# make_etf_great_again.net
KiCad netlist of a schematic drawn in Altium Designer
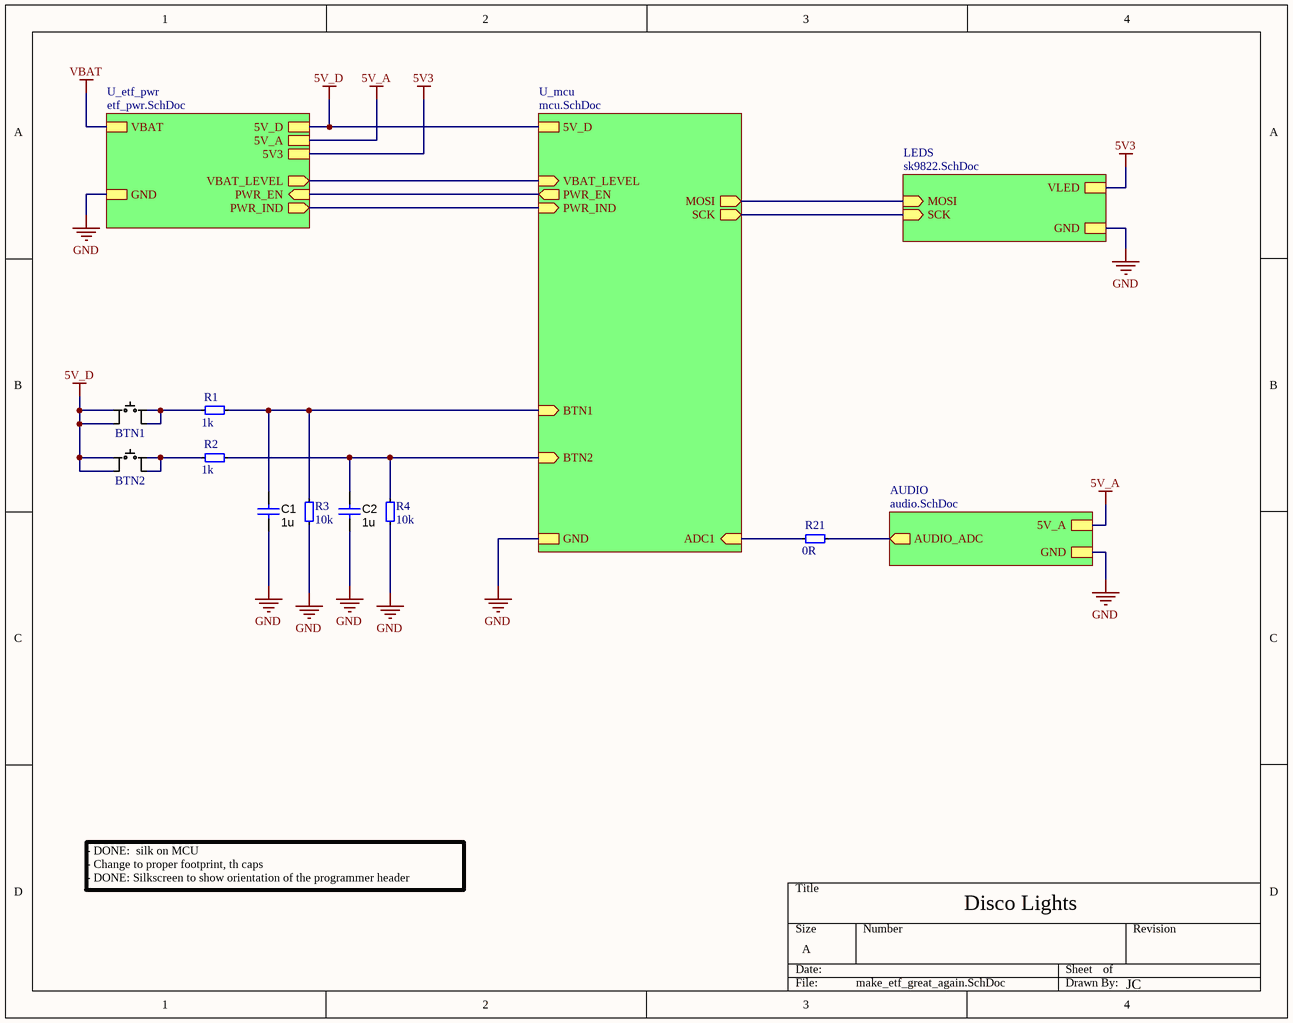
[diagram p0: make_etf_great_again.SchDoc]

(export (version "E")
  (design (tool "Eeschema 10.0.6"))
  (components
    (comp (ref "BTN1")
      (value "Tactile Button")
      (footprint "SW_TS02-66-150-BK-160-LCR-D")
      (description "Tactile Switch Small Low")
      (libsource (lib "urad") (part "TacButton TH"))
    )
    (comp (ref "BTN2")
      (value "Tactile Button")
      (footprint "SW_TS02-66-150-BK-160-LCR-D")
      (description "Tactile Switch Small Low")
      (libsource (lib "urad") (part "TacButton TH"))
    )
    (comp (ref "C1")
      (value "1u")
      (footprint "1206_180")
      (fields
        (field (name "JLCPCB PART #") "C1848")
        (field (name "MANUFACTURER PART NUMBER") "CC1206JKX7R7BB105")
        (field (name "Comment") "CAP, 1206")
      )
      (libsource (lib "urad") (part "CAP, 1206"))
    )
    (comp (ref "C2")
      (value "1u")
      (footprint "1206_180")
      (fields
        (field (name "JLCPCB PART #") "C1848")
        (field (name "MANUFACTURER PART NUMBER") "CC1206JKX7R7BB105")
        (field (name "Comment") "CAP, 1206")
      )
      (libsource (lib "urad") (part "CAP, 1206"))
    )
    (comp (ref "R1")
      (value "1k")
      (footprint "0603")
      (fields
        (field (name "JLCPCB PART #") "C21190")
        (field (name "MANUFACTURER PART NUMBER") "RC0603JR-070RL")
        (field (name "Comment") "0603, resistor")
      )
      (libsource (lib "jclib") (part "0603, resistor"))
    )
    (comp (ref "R2")
      (value "1k")
      (footprint "0603")
      (fields
        (field (name "JLCPCB PART #") "C21190")
        (field (name "MANUFACTURER PART NUMBER") "RC0603JR-070RL")
        (field (name "Comment") "0603, resistor")
      )
      (libsource (lib "jclib") (part "0603, resistor"))
    )
    (comp (ref "R3")
      (value "10k")
      (footprint "0603")
      (fields
        (field (name "JLCPCB PART #") "C98220")
        (field (name "MANUFACTURER PART NUMBER") "RC0603JR-070RL")
        (field (name "Comment") "0603, resistor")
      )
      (libsource (lib "jclib") (part "0603, resistor"))
    )
    (comp (ref "R4")
      (value "10k")
      (footprint "0603")
      (fields
        (field (name "JLCPCB PART #") "C98220")
        (field (name "MANUFACTURER PART NUMBER") "RC0603JR-070RL")
        (field (name "Comment") "0603, resistor")
      )
      (libsource (lib "jclib") (part "0603, resistor"))
    )
    (comp (ref "R21")
      (value "0R")
      (footprint "0603")
      (fields
        (field (name "JLCPCB PART #") "C95177")
        (field (name "MANUFACTURER PART NUMBER") "RC0603JR-070RL")
        (field (name "Comment") "0603, resistor")
      )
      (libsource (lib "jclib") (part "0603, resistor"))
    )
  )
  (nets
    (net (code "1") (name "/ADC1") (class "Default")
      (node (ref "R21") (pin "1") (pinfunction "1_1") (pintype "passive"))
    )
    (net (code "2") (name "/AUDIO_ADC") (class "Default")
      (node (ref "R21") (pin "0") (pinfunction "0_0") (pintype "passive"))
    )
    (net (code "3") (name "/BTN1") (class "Default")
      (node (ref "C1") (pin "1") (pinfunction "1_1") (pintype "passive"))
      (node (ref "R1") (pin "0") (pinfunction "0_0") (pintype "passive"))
      (node (ref "R3") (pin "0") (pinfunction "0_0") (pintype "passive"))
    )
    (net (code "4") (name "/BTN2") (class "Default")
      (node (ref "C2") (pin "1") (pinfunction "1_1") (pintype "passive"))
      (node (ref "R2") (pin "0") (pinfunction "0_0") (pintype "passive"))
      (node (ref "R4") (pin "0") (pinfunction "0_0") (pintype "passive"))
    )
    (net (code "12") (name "5V_D") (class "Default")
      (node (ref "BTN1") (pin "3") (pinfunction "3_3") (pintype "passive"))
      (node (ref "BTN1") (pin "4") (pinfunction "4_4") (pintype "passive"))
      (node (ref "BTN2") (pin "3") (pinfunction "3_3") (pintype "passive"))
      (node (ref "BTN2") (pin "4") (pinfunction "4_4") (pintype "passive"))
    )
    (net (code "13") (name "GND") (class "Default")
      (node (ref "C1") (pin "2") (pinfunction "2_2") (pintype "passive"))
      (node (ref "C2") (pin "2") (pinfunction "2_2") (pintype "passive"))
      (node (ref "R3") (pin "1") (pinfunction "1_1") (pintype "passive"))
      (node (ref "R4") (pin "1") (pinfunction "1_1") (pintype "passive"))
    )
    (net (code "14") (name "Net-(BTN1-Pad1)") (class "Default")
      (node (ref "BTN1") (pin "1") (pinfunction "1_1") (pintype "passive"))
      (node (ref "BTN1") (pin "2") (pinfunction "2_2") (pintype "passive"))
      (node (ref "R1") (pin "1") (pinfunction "1_1") (pintype "passive"))
    )
    (net (code "15") (name "Net-(BTN2-Pad1)") (class "Default")
      (node (ref "BTN2") (pin "1") (pinfunction "1_1") (pintype "passive"))
      (node (ref "BTN2") (pin "2") (pinfunction "2_2") (pintype "passive"))
      (node (ref "R2") (pin "1") (pinfunction "1_1") (pintype "passive"))
    )
  )
)
